# programmer_ICSP_atmega328.net
KiCad netlist of a schematic drawn in EAGLE
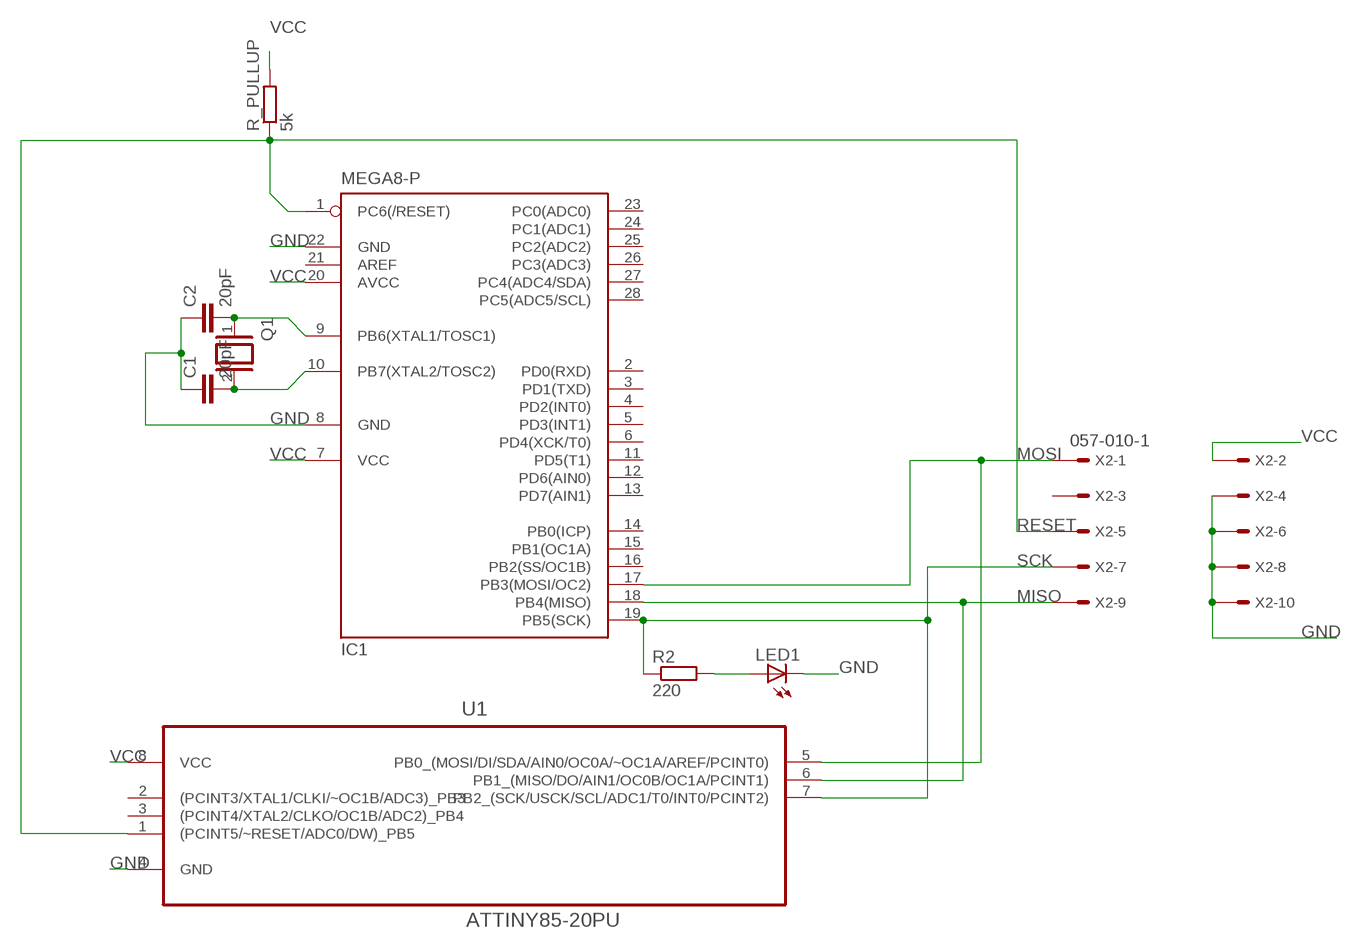
[diagram p0: schematic, sheet 1]

(export (version "E")
  (design (tool "Eeschema 10.0.6"))
  (components
    (comp (ref "C1")
      (value "20pF")
      (footprint "eagle-import:C5B5")
      (libsource (lib "eagle-import") (part "C5/5"))
    )
    (comp (ref "C2")
      (value "20pF")
      (footprint "eagle-import:C5B5")
      (libsource (lib "eagle-import") (part "C5/5"))
    )
    (comp (ref "IC1")
      (value "MEGA8-P")
      (footprint "eagle-import:DIL28-3")
      (libsource (lib "eagle-import") (part "MEGA8-P"))
    )
    (comp (ref "LED1")
      (value "LED3MM")
      (footprint "eagle-import:LED3MM")
      (libsource (lib "eagle-import") (part "LED3MM"))
    )
    (comp (ref "Q1")
      (value "XTAL/S")
      (footprint "eagle-import:QS")
      (libsource (lib "eagle-import") (part "XTAL/S"))
    )
    (comp (ref "R2")
      (value "220")
      (footprint "eagle-import:0207_7")
      (libsource (lib "eagle-import") (part "R-EU_0207/7"))
    )
    (comp (ref "R_PULLUP")
      (value "5k")
      (footprint "eagle-import:0207_7")
      (libsource (lib "eagle-import") (part "R-EU_0207/7"))
    )
    (comp (ref "U1")
      (value "ATTINY85-20PU")
      (footprint "eagle-import:DIP254P762X533-8")
      (libsource (lib "eagle-import") (part "ATTINY85-20PU"))
    )
    (comp (ref "X2")
      (value "057-010-1")
      (footprint "eagle-import:057-010-1")
      (libsource (lib "eagle-import") (part "057-010-1"))
    )
  )
  (nets
    (net (code "1") (name "/GND") (class "Default")
      (node (ref "C1") (pin "1") (pinfunction "1_1") (pintype "passive"))
      (node (ref "C2") (pin "1") (pinfunction "1_1") (pintype "passive"))
      (node (ref "IC1") (pin "22") (pinfunction "GND_22") (pintype "power_in"))
      (node (ref "IC1") (pin "8") (pinfunction "GND_8") (pintype "power_in"))
      (node (ref "LED1") (pin "K") (pinfunction "C_K") (pintype "passive"))
      (node (ref "U1") (pin "4") (pinfunction "GND_4") (pintype "passive"))
      (node (ref "X2") (pin "10") (pinfunction "S_10") (pintype "passive"))
      (node (ref "X2") (pin "4") (pinfunction "S_4") (pintype "passive"))
      (node (ref "X2") (pin "6") (pinfunction "S_6") (pintype "passive"))
      (node (ref "X2") (pin "8") (pinfunction "S_8") (pintype "passive"))
    )
    (net (code "2") (name "/MISO") (class "Default")
      (node (ref "IC1") (pin "18") (pinfunction "PB4(MISO)_18") (pintype "bidirectional"))
      (node (ref "U1") (pin "6") (pinfunction "PB1_(MISO/DO/AIN1/OC0B/OC1A/PCINT1)_6") (pintype "bidirectional"))
      (node (ref "X2") (pin "9") (pinfunction "S_9") (pintype "passive"))
    )
    (net (code "3") (name "/MOSI") (class "Default")
      (node (ref "IC1") (pin "17") (pinfunction "PB3(MOSI/OC2)_17") (pintype "bidirectional"))
      (node (ref "U1") (pin "5") (pinfunction "PB0_(MOSI/DI/SDA/AIN0/OC0A/~{OC1A/AREF/PCINT0})_5") (pintype "bidirectional"))
      (node (ref "X2") (pin "1") (pinfunction "S_1") (pintype "passive"))
    )
    (net (code "4") (name "/RESET") (class "Default")
      (node (ref "IC1") (pin "1") (pinfunction "PC6(/RESET)_1") (pintype "bidirectional"))
      (node (ref "R_PULLUP") (pin "1") (pinfunction "1_1") (pintype "passive"))
      (node (ref "U1") (pin "1") (pinfunction "(PCINT5/~{RESET/ADC0/DW})_PB5_1") (pintype "bidirectional"))
      (node (ref "X2") (pin "5") (pinfunction "S_5") (pintype "passive"))
    )
    (net (code "5") (name "/SCK") (class "Default")
      (node (ref "IC1") (pin "19") (pinfunction "PB5(SCK)_19") (pintype "bidirectional"))
      (node (ref "R2") (pin "1") (pinfunction "1_1") (pintype "passive"))
      (node (ref "U1") (pin "7") (pinfunction "PB2_(SCK/USCK/SCL/ADC1/T0/INT0/PCINT2)_7") (pintype "bidirectional"))
      (node (ref "X2") (pin "7") (pinfunction "S_7") (pintype "passive"))
    )
    (net (code "6") (name "/VCC") (class "Default")
      (node (ref "IC1") (pin "20") (pinfunction "AVCC_20") (pintype "power_in"))
      (node (ref "IC1") (pin "7") (pinfunction "VCC_7") (pintype "power_in"))
      (node (ref "R_PULLUP") (pin "2") (pinfunction "2_2") (pintype "passive"))
      (node (ref "U1") (pin "8") (pinfunction "VCC_8") (pintype "power_in"))
      (node (ref "X2") (pin "2") (pinfunction "S_2") (pintype "passive"))
    )
    (net (code "7") (name "Net-(IC1-PB6(XTAL1{slash}TOSC1))") (class "Default")
      (node (ref "C2") (pin "2") (pinfunction "2_2") (pintype "passive"))
      (node (ref "IC1") (pin "9") (pinfunction "PB6(XTAL1/TOSC1)_9") (pintype "bidirectional"))
      (node (ref "Q1") (pin "1") (pinfunction "1_1") (pintype "passive"))
    )
    (net (code "8") (name "Net-(IC1-PB7(XTAL2{slash}TOSC2))") (class "Default")
      (node (ref "C1") (pin "2") (pinfunction "2_2") (pintype "passive"))
      (node (ref "IC1") (pin "10") (pinfunction "PB7(XTAL2/TOSC2)_10") (pintype "bidirectional"))
      (node (ref "Q1") (pin "2") (pinfunction "2_2") (pintype "passive"))
    )
    (net (code "9") (name "Net-(LED1-PadA)") (class "Default")
      (node (ref "LED1") (pin "A") (pinfunction "A_A") (pintype "passive"))
      (node (ref "R2") (pin "2") (pinfunction "2_2") (pintype "passive"))
    )
    (net (code "10") (name "unconnected-(IC1-AREF-Pad21)") (class "Default")
      (node (ref "IC1") (pin "21") (pinfunction "AREF_21") (pintype "passive"))
    )
    (net (code "11") (name "unconnected-(IC1-PB0(ICP)-Pad14)") (class "Default")
      (node (ref "IC1") (pin "14") (pinfunction "PB0(ICP)_14") (pintype "bidirectional"))
    )
    (net (code "12") (name "unconnected-(IC1-PB1(OC1A)-Pad15)") (class "Default")
      (node (ref "IC1") (pin "15") (pinfunction "PB1(OC1A)_15") (pintype "bidirectional"))
    )
    (net (code "13") (name "unconnected-(IC1-PB2(SS{slash}OC1B)-Pad16)") (class "Default")
      (node (ref "IC1") (pin "16") (pinfunction "PB2(SS/OC1B)_16") (pintype "bidirectional"))
    )
    (net (code "14") (name "unconnected-(IC1-PC0(ADC0)-Pad23)") (class "Default")
      (node (ref "IC1") (pin "23") (pinfunction "PC0(ADC0)_23") (pintype "bidirectional"))
    )
    (net (code "15") (name "unconnected-(IC1-PC1(ADC1)-Pad24)") (class "Default")
      (node (ref "IC1") (pin "24") (pinfunction "PC1(ADC1)_24") (pintype "bidirectional"))
    )
    (net (code "16") (name "unconnected-(IC1-PC2(ADC2)-Pad25)") (class "Default")
      (node (ref "IC1") (pin "25") (pinfunction "PC2(ADC2)_25") (pintype "bidirectional"))
    )
    (net (code "17") (name "unconnected-(IC1-PC3(ADC3)-Pad26)") (class "Default")
      (node (ref "IC1") (pin "26") (pinfunction "PC3(ADC3)_26") (pintype "bidirectional"))
    )
    (net (code "18") (name "unconnected-(IC1-PC4(ADC4{slash}SDA)-Pad27)") (class "Default")
      (node (ref "IC1") (pin "27") (pinfunction "PC4(ADC4/SDA)_27") (pintype "bidirectional"))
    )
    (net (code "19") (name "unconnected-(IC1-PC5(ADC5{slash}SCL)-Pad28)") (class "Default")
      (node (ref "IC1") (pin "28") (pinfunction "PC5(ADC5/SCL)_28") (pintype "bidirectional"))
    )
    (net (code "20") (name "unconnected-(IC1-PD0(RXD)-Pad2)") (class "Default")
      (node (ref "IC1") (pin "2") (pinfunction "PD0(RXD)_2") (pintype "bidirectional"))
    )
    (net (code "21") (name "unconnected-(IC1-PD1(TXD)-Pad3)") (class "Default")
      (node (ref "IC1") (pin "3") (pinfunction "PD1(TXD)_3") (pintype "bidirectional"))
    )
    (net (code "22") (name "unconnected-(IC1-PD2(INT0)-Pad4)") (class "Default")
      (node (ref "IC1") (pin "4") (pinfunction "PD2(INT0)_4") (pintype "bidirectional"))
    )
    (net (code "23") (name "unconnected-(IC1-PD3(INT1)-Pad5)") (class "Default")
      (node (ref "IC1") (pin "5") (pinfunction "PD3(INT1)_5") (pintype "bidirectional"))
    )
    (net (code "24") (name "unconnected-(IC1-PD4(XCK{slash}T0)-Pad6)") (class "Default")
      (node (ref "IC1") (pin "6") (pinfunction "PD4(XCK/T0)_6") (pintype "bidirectional"))
    )
    (net (code "25") (name "unconnected-(IC1-PD5(T1)-Pad11)") (class "Default")
      (node (ref "IC1") (pin "11") (pinfunction "PD5(T1)_11") (pintype "bidirectional"))
    )
    (net (code "26") (name "unconnected-(IC1-PD6(AIN0)-Pad12)") (class "Default")
      (node (ref "IC1") (pin "12") (pinfunction "PD6(AIN0)_12") (pintype "bidirectional"))
    )
    (net (code "27") (name "unconnected-(IC1-PD7(AIN1)-Pad13)") (class "Default")
      (node (ref "IC1") (pin "13") (pinfunction "PD7(AIN1)_13") (pintype "bidirectional"))
    )
    (net (code "28") (name "unconnected-(U1-(PCINT3{slash}XTAL1{slash}CLKI{slash}~{OC1B{slash}ADC3})_PB3-Pad2)") (class "Default")
      (node (ref "U1") (pin "2") (pinfunction "(PCINT3/XTAL1/CLKI/~{OC1B/ADC3})_PB3_2") (pintype "bidirectional"))
    )
    (net (code "29") (name "unconnected-(U1-(PCINT4{slash}XTAL2{slash}CLKO{slash}OC1B{slash}ADC2)_PB4-Pad3)") (class "Default")
      (node (ref "U1") (pin "3") (pinfunction "(PCINT4/XTAL2/CLKO/OC1B/ADC2)_PB4_3") (pintype "bidirectional"))
    )
    (net (code "30") (name "unconnected-(X2D-S-Pad3)") (class "Default")
      (node (ref "X2") (pin "3") (pinfunction "S_3") (pintype "passive"))
    )
  )
)
